# OnBoardStampedMetal_Antenna.net
KiCad netlist of a schematic drawn in EAGLE
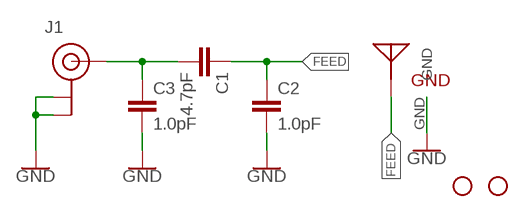
[diagram p0: schematic, sheet 1]

(export (version "E")
  (design (tool "Eeschema 10.0.6"))
  (components
    (comp (ref "C1")
      (value "4.7pF")
      (footprint "eagle-import:0603")
      (libsource (lib "eagle-import") (part "4.7PF-0603-50V-5%"))
    )
    (comp (ref "C2")
      (value "1.0pF")
      (footprint "eagle-import:0603")
      (libsource (lib "eagle-import") (part "1.0PF-0603-50V-25%"))
    )
    (comp (ref "C3")
      (value "1.0pF")
      (footprint "eagle-import:0603")
      (libsource (lib "eagle-import") (part "1.0PF-0603-50V-25%"))
    )
    (comp (ref "H1")
      (value "STAND-OFF")
      (footprint "eagle-import:STAND-OFF")
      (libsource (lib "eagle-import") (part "STAND-OFF"))
    )
    (comp (ref "H2")
      (value "STAND-OFF")
      (footprint "eagle-import:STAND-OFF")
      (libsource (lib "eagle-import") (part "STAND-OFF"))
    )
    (comp (ref "J1")
      (value "U.FL")
      (footprint "eagle-import:U.FL")
      (libsource (lib "eagle-import") (part "U.FL"))
    )
    (comp (ref "U$1")
      (value "ONBOARD_SMD_STAMPED")
      (footprint "eagle-import:ONBOARD_SMD_STAMPED")
      (libsource (lib "eagle-import") (part "ONBOARD_SMD_STAMPED"))
    )
  )
  (nets
    (net (code "1") (name "FEED") (class "Default")
      (node (ref "C1") (pin "1") (pinfunction "1_1") (pintype "passive"))
      (node (ref "C2") (pin "1") (pinfunction "1_1") (pintype "passive"))
      (node (ref "U$1") (pin "FEED") (pinfunction "FEED_FEED") (pintype "bidirectional"))
    )
    (net (code "2") (name "GND") (class "Default")
      (node (ref "C2") (pin "2") (pinfunction "2_2") (pintype "passive"))
      (node (ref "C3") (pin "2") (pinfunction "2_2") (pintype "passive"))
      (node (ref "J1") (pin "1") (pinfunction "GND_1") (pintype "bidirectional"))
      (node (ref "J1") (pin "2") (pinfunction "GND_2") (pintype "bidirectional"))
      (node (ref "U$1") (pin "GND") (pinfunction "GND_GND") (pintype "bidirectional"))
    )
    (net (code "3") (name "Net-(J1-SIGNAL)") (class "Default")
      (node (ref "C1") (pin "2") (pinfunction "2_2") (pintype "passive"))
      (node (ref "C3") (pin "1") (pinfunction "1_1") (pintype "passive"))
      (node (ref "J1") (pin "FEED") (pinfunction "SIGNAL_FEED") (pintype "bidirectional"))
    )
  )
)
